# ISO_I2C.net
KiCad netlist of a schematic drawn in Altium Designer
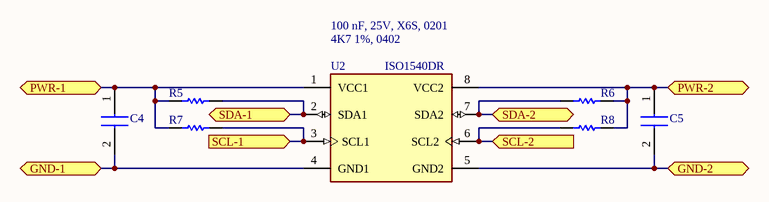
[diagram p0: ISO_I2C.SchDoc]

(export (version "E")
  (design (tool "Eeschema 10.0.6"))
  (components
    (comp (ref "C4")
      (value "100 nF, 25V, X6S, 0201")
      (footprint "SamacSys:CAPC0603X33N")
      (description "Capacitor")
      (fields
        (field (name "MANUFACTURER_PART_NUMBER") "GRM033C81E104KE14D")
        (field (name "MOUSER PART NUMBER") "81-GRM33C81E104KE14D")
      )
      (libsource (lib "*") (part "GRM033C81E104KE14D"))
    )
    (comp (ref "C5")
      (value "100 nF, 25V, X6S, 0201")
      (footprint "SamacSys:CAPC0603X33N")
      (description "Capacitor")
      (fields
        (field (name "MANUFACTURER_PART_NUMBER") "GRM033C81E104KE14D")
        (field (name "MOUSER PART NUMBER") "81-GRM33C81E104KE14D")
      )
      (libsource (lib "*") (part "GRM033C81E104KE14D"))
    )
    (comp (ref "R5")
      (value "4K7 1%, 0402")
      (footprint "RESC1005X40X25LL05T05")
      (description "Chip Resistor, 4.7 KOhm, +/- 1%, 0.1 W, -55 to 155 degC, 0402 (1005 Metric), RoHS, Tape and Reel")
      (fields (field (name "TOLERANCE") "1%") (field (name "PARTNUMBER") "ERJ-2RKF4701X"))
      (libsource (lib "Altium Content Vault") (part "RES-2"))
    )
    (comp (ref "R6")
      (value "4K7 1%, 0402")
      (footprint "RESC1005X40X25LL05T05")
      (description "Chip Resistor, 4.7 KOhm, +/- 1%, 0.1 W, -55 to 155 degC, 0402 (1005 Metric), RoHS, Tape and Reel")
      (fields (field (name "TOLERANCE") "1%") (field (name "PARTNUMBER") "ERJ-2RKF4701X"))
      (libsource (lib "Altium Content Vault") (part "RES-2"))
    )
    (comp (ref "R7")
      (value "4K7 1%, 0402")
      (footprint "RESC1005X40X25LL05T05")
      (description "Chip Resistor, 4.7 KOhm, +/- 1%, 0.1 W, -55 to 155 degC, 0402 (1005 Metric), RoHS, Tape and Reel")
      (fields (field (name "TOLERANCE") "1%") (field (name "PARTNUMBER") "ERJ-2RKF4701X"))
      (libsource (lib "Altium Content Vault") (part "RES-2"))
    )
    (comp (ref "R8")
      (value "4K7 1%, 0402")
      (footprint "RESC1005X40X25LL05T05")
      (description "Chip Resistor, 4.7 KOhm, +/- 1%, 0.1 W, -55 to 155 degC, 0402 (1005 Metric), RoHS, Tape and Reel")
      (fields (field (name "TOLERANCE") "1%") (field (name "PARTNUMBER") "ERJ-2RKF4701X"))
      (libsource (lib "Altium Content Vault") (part "RES-2"))
    )
    (comp (ref "U2")
      (value "ISO1540DR")
      (footprint "FP-D0008A-MFG")
      (description "DGTL ISO 2.5KV 2CH I2C 8SOIC")
      (fields
        (field (name "OCTOPART") "https://octopart.com/iso1540dr-texas+instruments-24334113")
        (field (name "MANUFACTURER") "Texas Instruments")
      )
      (libsource (lib "Altium Content Vault") (part "d824faccee5d143ad01692c0ddd1d85"))
    )
  )
  (nets
    (net (code "1") (name "/GND-1") (class "Default")
      (node (ref "C4") (pin "2") (pinfunction "2_2") (pintype "passive"))
      (node (ref "U2") (pin "4") (pinfunction "GND1_4") (pintype "power_in"))
    )
    (net (code "2") (name "/GND-2") (class "Default")
      (node (ref "C5") (pin "2") (pinfunction "2_2") (pintype "passive"))
      (node (ref "U2") (pin "5") (pinfunction "GND2_5") (pintype "power_in"))
    )
    (net (code "3") (name "/PWR-1") (class "Default")
      (node (ref "C4") (pin "1") (pinfunction "1_1") (pintype "passive"))
      (node (ref "R5") (pin "2") (pinfunction "2_2") (pintype "passive"))
      (node (ref "R7") (pin "2") (pinfunction "2_2") (pintype "passive"))
      (node (ref "U2") (pin "1") (pinfunction "VCC1_1") (pintype "power_in"))
    )
    (net (code "4") (name "/PWR-2") (class "Default")
      (node (ref "C5") (pin "1") (pinfunction "1_1") (pintype "passive"))
      (node (ref "R6") (pin "1") (pinfunction "1_1") (pintype "passive"))
      (node (ref "R8") (pin "1") (pinfunction "1_1") (pintype "passive"))
      (node (ref "U2") (pin "8") (pinfunction "VCC2_8") (pintype "power_in"))
    )
    (net (code "5") (name "/SCL-1") (class "Default")
      (node (ref "R7") (pin "1") (pinfunction "1_1") (pintype "passive"))
      (node (ref "U2") (pin "3") (pinfunction "SCL1_3") (pintype "input"))
    )
    (net (code "6") (name "/SCL-2") (class "Default")
      (node (ref "R8") (pin "2") (pinfunction "2_2") (pintype "passive"))
      (node (ref "U2") (pin "6") (pinfunction "SCL2_6") (pintype "input"))
    )
    (net (code "7") (name "/SDA-1") (class "Default")
      (node (ref "R5") (pin "1") (pinfunction "1_1") (pintype "passive"))
      (node (ref "U2") (pin "2") (pinfunction "SDA1_2") (pintype "bidirectional"))
    )
    (net (code "8") (name "/SDA-2") (class "Default")
      (node (ref "R6") (pin "2") (pinfunction "2_2") (pintype "passive"))
      (node (ref "U2") (pin "7") (pinfunction "SDA2_7") (pintype "bidirectional"))
    )
  )
)
